# SBX_connector_outline.net
KiCad netlist of a schematic drawn in EAGLE
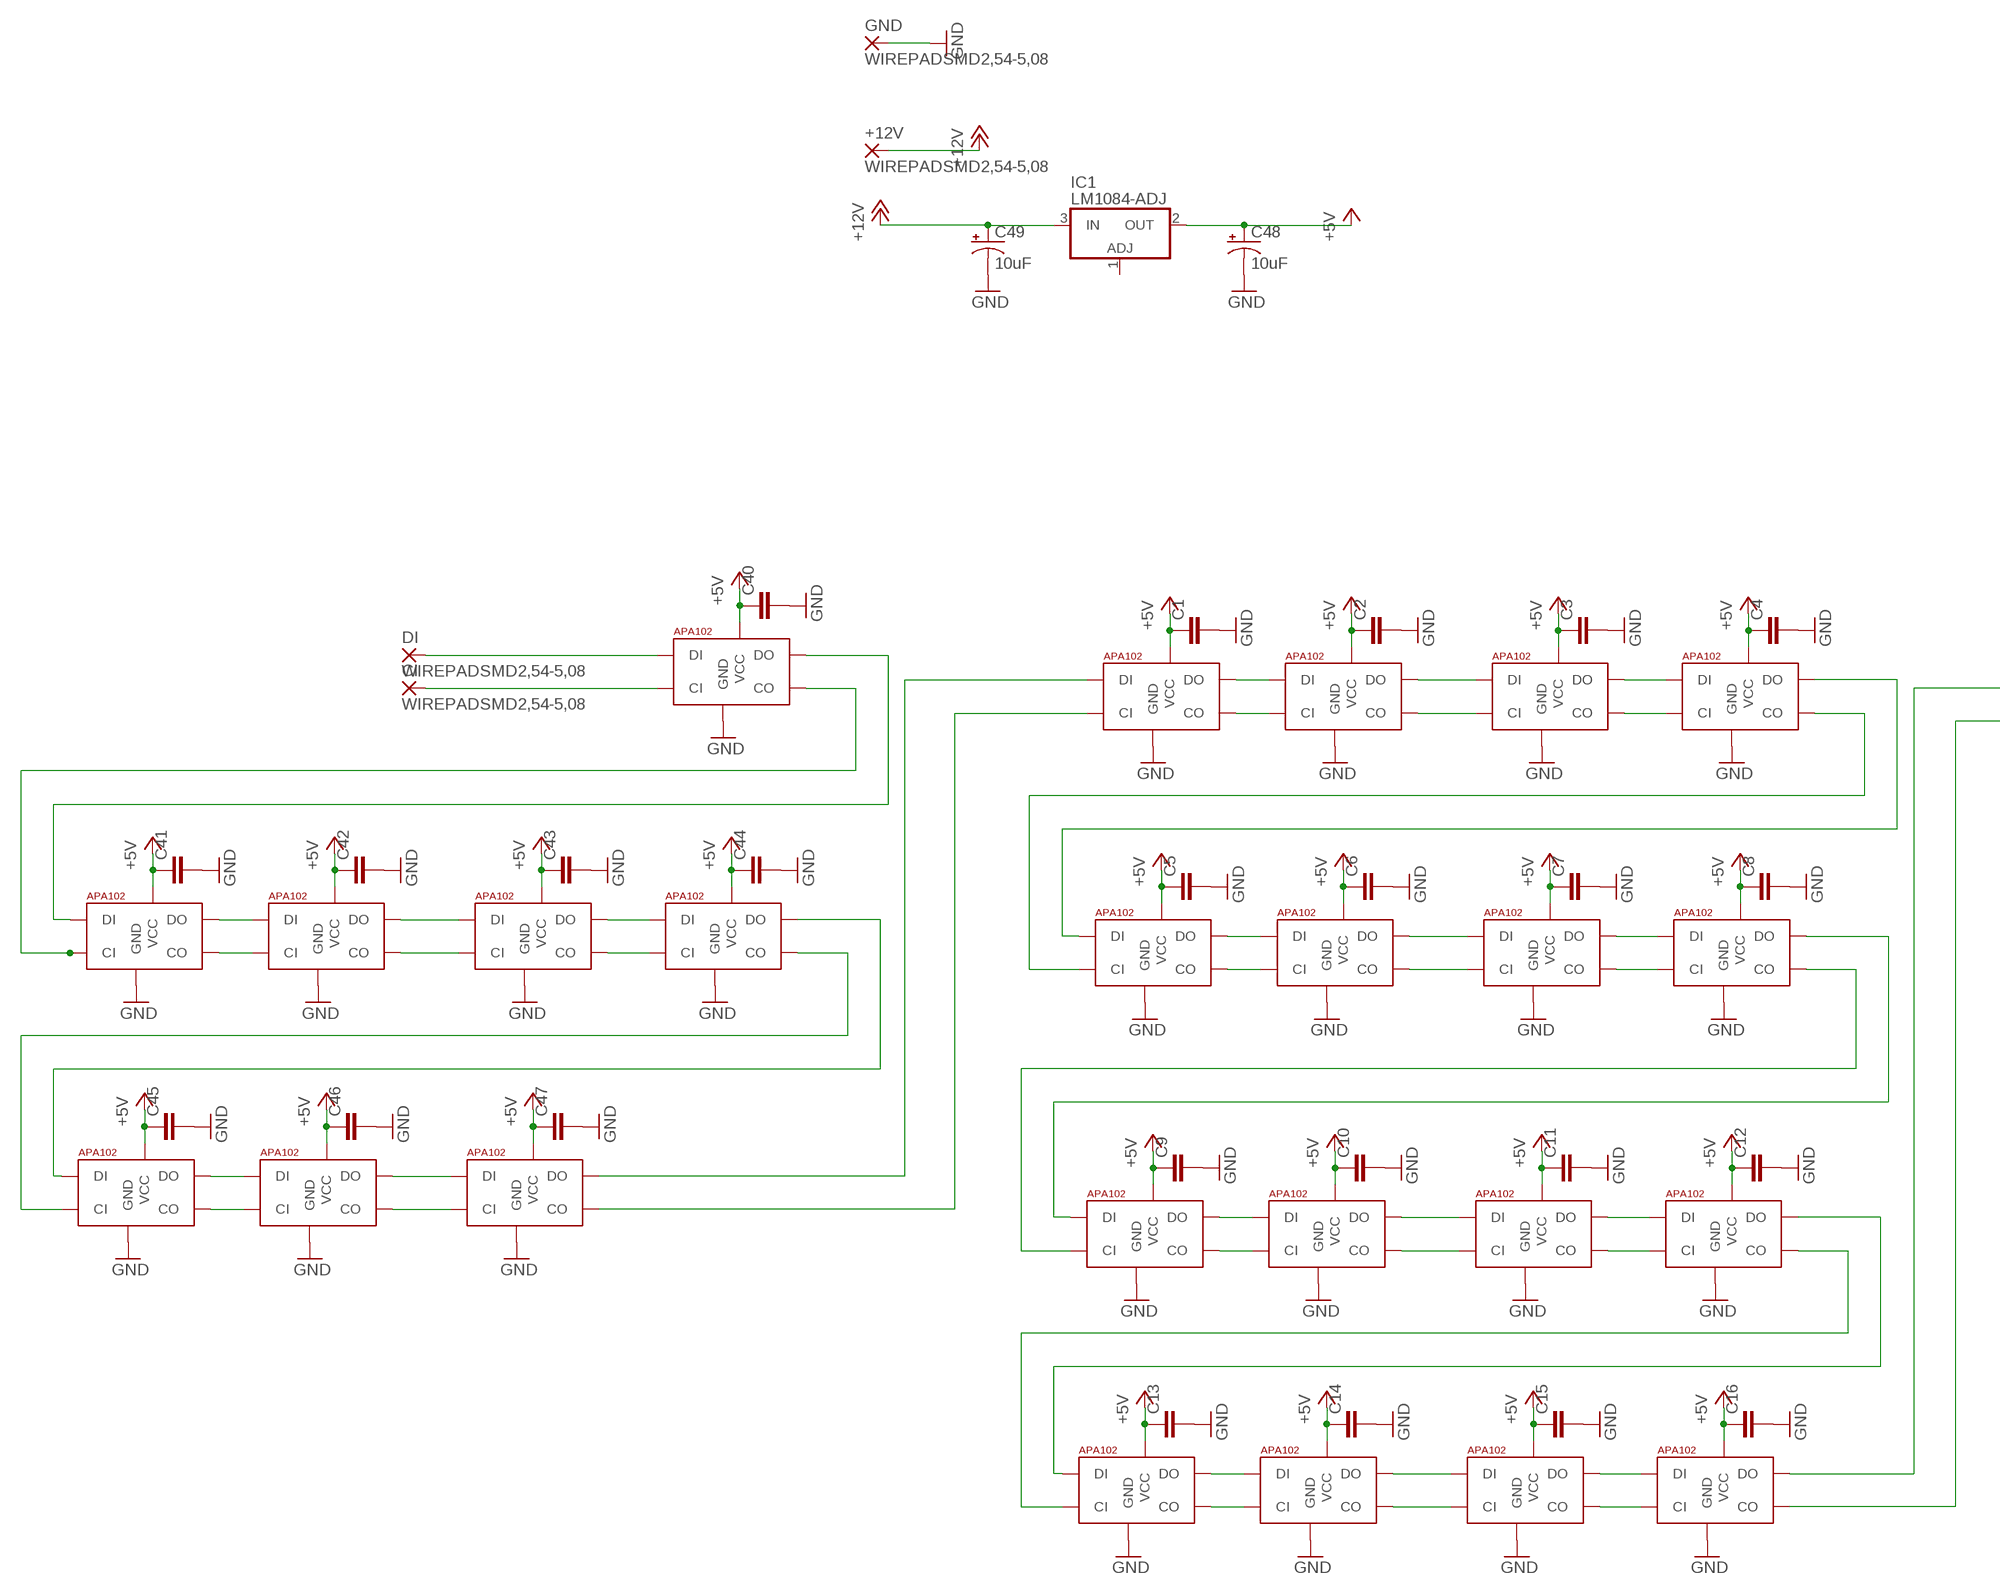
[diagram p0: schematic, sheet 1, part 1 of 2]
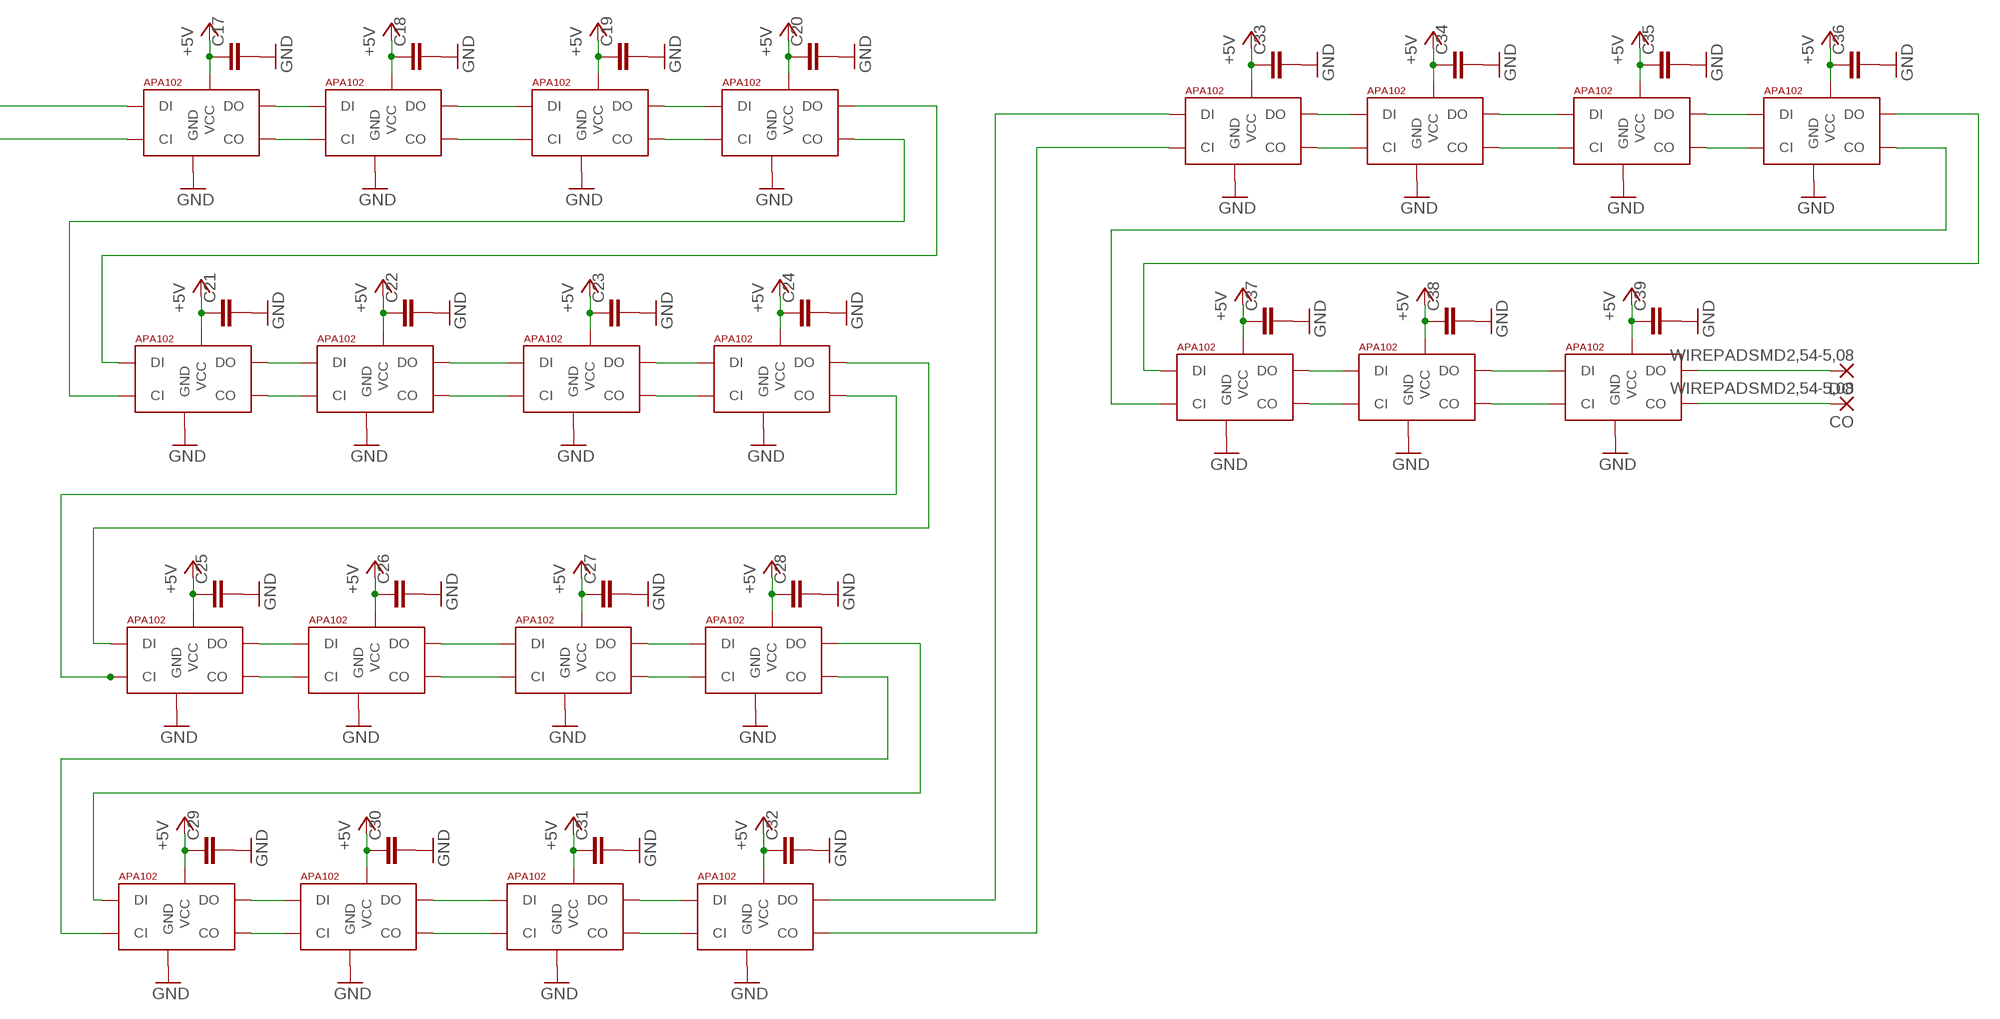
[diagram p1: schematic, sheet 1, part 2 of 2]

(export (version "E")
  (design (tool "Eeschema 10.0.6"))
  (components
    (comp (ref "+12V")
      (value "WIREPADSMD2,54-5,08")
      (footprint "eagle-import:SMD2,54-5,08")
      (libsource (lib "eagle-import") (part "WIREPADSMD2,54-5,08"))
    )
    (comp (ref "C1")
      (value "CAP0603-CAP")
      (footprint "eagle-import:0603-CAP")
      (libsource (lib "eagle-import") (part "CAP0603-CAP"))
    )
    (comp (ref "C2")
      (value "CAP0603-CAP")
      (footprint "eagle-import:0603-CAP")
      (libsource (lib "eagle-import") (part "CAP0603-CAP"))
    )
    (comp (ref "C3")
      (value "CAP0603-CAP")
      (footprint "eagle-import:0603-CAP")
      (libsource (lib "eagle-import") (part "CAP0603-CAP"))
    )
    (comp (ref "C4")
      (value "CAP0603-CAP")
      (footprint "eagle-import:0603-CAP")
      (libsource (lib "eagle-import") (part "CAP0603-CAP"))
    )
    (comp (ref "C5")
      (value "CAP0603-CAP")
      (footprint "eagle-import:0603-CAP")
      (libsource (lib "eagle-import") (part "CAP0603-CAP"))
    )
    (comp (ref "C6")
      (value "CAP0603-CAP")
      (footprint "eagle-import:0603-CAP")
      (libsource (lib "eagle-import") (part "CAP0603-CAP"))
    )
    (comp (ref "C7")
      (value "CAP0603-CAP")
      (footprint "eagle-import:0603-CAP")
      (libsource (lib "eagle-import") (part "CAP0603-CAP"))
    )
    (comp (ref "C8")
      (value "CAP0603-CAP")
      (footprint "eagle-import:0603-CAP")
      (libsource (lib "eagle-import") (part "CAP0603-CAP"))
    )
    (comp (ref "C9")
      (value "CAP0603-CAP")
      (footprint "eagle-import:0603-CAP")
      (libsource (lib "eagle-import") (part "CAP0603-CAP"))
    )
    (comp (ref "C10")
      (value "CAP0603-CAP")
      (footprint "eagle-import:0603-CAP")
      (libsource (lib "eagle-import") (part "CAP0603-CAP"))
    )
    (comp (ref "C11")
      (value "CAP0603-CAP")
      (footprint "eagle-import:0603-CAP")
      (libsource (lib "eagle-import") (part "CAP0603-CAP"))
    )
    (comp (ref "C12")
      (value "CAP0603-CAP")
      (footprint "eagle-import:0603-CAP")
      (libsource (lib "eagle-import") (part "CAP0603-CAP"))
    )
    (comp (ref "C13")
      (value "CAP0603-CAP")
      (footprint "eagle-import:0603-CAP")
      (libsource (lib "eagle-import") (part "CAP0603-CAP"))
    )
    (comp (ref "C14")
      (value "CAP0603-CAP")
      (footprint "eagle-import:0603-CAP")
      (libsource (lib "eagle-import") (part "CAP0603-CAP"))
    )
    (comp (ref "C15")
      (value "CAP0603-CAP")
      (footprint "eagle-import:0603-CAP")
      (libsource (lib "eagle-import") (part "CAP0603-CAP"))
    )
    (comp (ref "C16")
      (value "CAP0603-CAP")
      (footprint "eagle-import:0603-CAP")
      (libsource (lib "eagle-import") (part "CAP0603-CAP"))
    )
    (comp (ref "C17")
      (value "CAP0603-CAP")
      (footprint "eagle-import:0603-CAP")
      (libsource (lib "eagle-import") (part "CAP0603-CAP"))
    )
    (comp (ref "C18")
      (value "CAP0603-CAP")
      (footprint "eagle-import:0603-CAP")
      (libsource (lib "eagle-import") (part "CAP0603-CAP"))
    )
    (comp (ref "C19")
      (value "CAP0603-CAP")
      (footprint "eagle-import:0603-CAP")
      (libsource (lib "eagle-import") (part "CAP0603-CAP"))
    )
    (comp (ref "C20")
      (value "CAP0603-CAP")
      (footprint "eagle-import:0603-CAP")
      (libsource (lib "eagle-import") (part "CAP0603-CAP"))
    )
    (comp (ref "C21")
      (value "CAP0603-CAP")
      (footprint "eagle-import:0603-CAP")
      (libsource (lib "eagle-import") (part "CAP0603-CAP"))
    )
    (comp (ref "C22")
      (value "CAP0603-CAP")
      (footprint "eagle-import:0603-CAP")
      (libsource (lib "eagle-import") (part "CAP0603-CAP"))
    )
    (comp (ref "C23")
      (value "CAP0603-CAP")
      (footprint "eagle-import:0603-CAP")
      (libsource (lib "eagle-import") (part "CAP0603-CAP"))
    )
    (comp (ref "C24")
      (value "CAP0603-CAP")
      (footprint "eagle-import:0603-CAP")
      (libsource (lib "eagle-import") (part "CAP0603-CAP"))
    )
    (comp (ref "C25")
      (value "CAP0603-CAP")
      (footprint "eagle-import:0603-CAP")
      (libsource (lib "eagle-import") (part "CAP0603-CAP"))
    )
    (comp (ref "C26")
      (value "CAP0603-CAP")
      (footprint "eagle-import:0603-CAP")
      (libsource (lib "eagle-import") (part "CAP0603-CAP"))
    )
    (comp (ref "C27")
      (value "CAP0603-CAP")
      (footprint "eagle-import:0603-CAP")
      (libsource (lib "eagle-import") (part "CAP0603-CAP"))
    )
    (comp (ref "C28")
      (value "CAP0603-CAP")
      (footprint "eagle-import:0603-CAP")
      (libsource (lib "eagle-import") (part "CAP0603-CAP"))
    )
    (comp (ref "C29")
      (value "CAP0603-CAP")
      (footprint "eagle-import:0603-CAP")
      (libsource (lib "eagle-import") (part "CAP0603-CAP"))
    )
    (comp (ref "C30")
      (value "CAP0603-CAP")
      (footprint "eagle-import:0603-CAP")
      (libsource (lib "eagle-import") (part "CAP0603-CAP"))
    )
    (comp (ref "C31")
      (value "CAP0603-CAP")
      (footprint "eagle-import:0603-CAP")
      (libsource (lib "eagle-import") (part "CAP0603-CAP"))
    )
    (comp (ref "C32")
      (value "CAP0603-CAP")
      (footprint "eagle-import:0603-CAP")
      (libsource (lib "eagle-import") (part "CAP0603-CAP"))
    )
    (comp (ref "C33")
      (value "CAP0603-CAP")
      (footprint "eagle-import:0603-CAP")
      (libsource (lib "eagle-import") (part "CAP0603-CAP"))
    )
    (comp (ref "C34")
      (value "CAP0603-CAP")
      (footprint "eagle-import:0603-CAP")
      (libsource (lib "eagle-import") (part "CAP0603-CAP"))
    )
    (comp (ref "C35")
      (value "CAP0603-CAP")
      (footprint "eagle-import:0603-CAP")
      (libsource (lib "eagle-import") (part "CAP0603-CAP"))
    )
    (comp (ref "C36")
      (value "CAP0603-CAP")
      (footprint "eagle-import:0603-CAP")
      (libsource (lib "eagle-import") (part "CAP0603-CAP"))
    )
    (comp (ref "C37")
      (value "CAP0603-CAP")
      (footprint "eagle-import:0603-CAP")
      (libsource (lib "eagle-import") (part "CAP0603-CAP"))
    )
    (comp (ref "C38")
      (value "CAP0603-CAP")
      (footprint "eagle-import:0603-CAP")
      (libsource (lib "eagle-import") (part "CAP0603-CAP"))
    )
    (comp (ref "C39")
      (value "CAP0603-CAP")
      (footprint "eagle-import:0603-CAP")
      (libsource (lib "eagle-import") (part "CAP0603-CAP"))
    )
    (comp (ref "C40")
      (value "CAP0603-CAP")
      (footprint "eagle-import:0603-CAP")
      (libsource (lib "eagle-import") (part "CAP0603-CAP"))
    )
    (comp (ref "C41")
      (value "CAP0603-CAP")
      (footprint "eagle-import:0603-CAP")
      (libsource (lib "eagle-import") (part "CAP0603-CAP"))
    )
    (comp (ref "C42")
      (value "CAP0603-CAP")
      (footprint "eagle-import:0603-CAP")
      (libsource (lib "eagle-import") (part "CAP0603-CAP"))
    )
    (comp (ref "C43")
      (value "CAP0603-CAP")
      (footprint "eagle-import:0603-CAP")
      (libsource (lib "eagle-import") (part "CAP0603-CAP"))
    )
    (comp (ref "C44")
      (value "CAP0603-CAP")
      (footprint "eagle-import:0603-CAP")
      (libsource (lib "eagle-import") (part "CAP0603-CAP"))
    )
    (comp (ref "C45")
      (value "CAP0603-CAP")
      (footprint "eagle-import:0603-CAP")
      (libsource (lib "eagle-import") (part "CAP0603-CAP"))
    )
    (comp (ref "C46")
      (value "CAP0603-CAP")
      (footprint "eagle-import:0603-CAP")
      (libsource (lib "eagle-import") (part "CAP0603-CAP"))
    )
    (comp (ref "C47")
      (value "CAP0603-CAP")
      (footprint "eagle-import:0603-CAP")
      (libsource (lib "eagle-import") (part "CAP0603-CAP"))
    )
    (comp (ref "C48")
      (value "10uF")
      (footprint "eagle-import:EIA3216")
      (libsource (lib "eagle-import") (part "10UF-TANT"))
    )
    (comp (ref "C49")
      (value "10uF")
      (footprint "eagle-import:EIA3216")
      (libsource (lib "eagle-import") (part "10UF-TANT"))
    )
    (comp (ref "CI")
      (value "WIREPADSMD2,54-5,08")
      (footprint "eagle-import:SMD2,54-5,08")
      (libsource (lib "eagle-import") (part "WIREPADSMD2,54-5,08"))
    )
    (comp (ref "CO")
      (value "WIREPADSMD2,54-5,08")
      (footprint "eagle-import:SMD2,54-5,08")
      (libsource (lib "eagle-import") (part "WIREPADSMD2,54-5,08"))
    )
    (comp (ref "DI")
      (value "WIREPADSMD2,54-5,08")
      (footprint "eagle-import:SMD2,54-5,08")
      (libsource (lib "eagle-import") (part "WIREPADSMD2,54-5,08"))
    )
    (comp (ref "DO")
      (value "WIREPADSMD2,54-5,08")
      (footprint "eagle-import:SMD2,54-5,08")
      (libsource (lib "eagle-import") (part "WIREPADSMD2,54-5,08"))
    )
    (comp (ref "GND")
      (value "WIREPADSMD2,54-5,08")
      (footprint "eagle-import:SMD2,54-5,08")
      (libsource (lib "eagle-import") (part "WIREPADSMD2,54-5,08"))
    )
    (comp (ref "IC1")
      (value "LM1084-ADJ")
      (footprint "eagle-import:TO263-3")
      (libsource (lib "eagle-import") (part "LM1084-ADJ"))
    )
    (comp (ref "U$1")
      (value "APA1025050")
      (footprint "eagle-import:APA102_5050")
      (libsource (lib "eagle-import") (part "APA1025050"))
    )
    (comp (ref "U$2")
      (value "APA1025050")
      (footprint "eagle-import:APA102_5050")
      (libsource (lib "eagle-import") (part "APA1025050"))
    )
    (comp (ref "U$3")
      (value "APA1025050")
      (footprint "eagle-import:APA102_5050")
      (libsource (lib "eagle-import") (part "APA1025050"))
    )
    (comp (ref "U$4")
      (value "APA1025050")
      (footprint "eagle-import:APA102_5050")
      (libsource (lib "eagle-import") (part "APA1025050"))
    )
    (comp (ref "U$5")
      (value "APA1025050")
      (footprint "eagle-import:APA102_5050")
      (libsource (lib "eagle-import") (part "APA1025050"))
    )
    (comp (ref "U$6")
      (value "APA1025050")
      (footprint "eagle-import:APA102_5050")
      (libsource (lib "eagle-import") (part "APA1025050"))
    )
    (comp (ref "U$7")
      (value "APA1025050")
      (footprint "eagle-import:APA102_5050")
      (libsource (lib "eagle-import") (part "APA1025050"))
    )
    (comp (ref "U$8")
      (value "APA1025050")
      (footprint "eagle-import:APA102_5050")
      (libsource (lib "eagle-import") (part "APA1025050"))
    )
    (comp (ref "U$9")
      (value "APA1025050")
      (footprint "eagle-import:APA102_5050")
      (libsource (lib "eagle-import") (part "APA1025050"))
    )
    (comp (ref "U$10")
      (value "APA1025050")
      (footprint "eagle-import:APA102_5050")
      (libsource (lib "eagle-import") (part "APA1025050"))
    )
    (comp (ref "U$11")
      (value "APA1025050")
      (footprint "eagle-import:APA102_5050")
      (libsource (lib "eagle-import") (part "APA1025050"))
    )
    (comp (ref "U$12")
      (value "APA1025050")
      (footprint "eagle-import:APA102_5050")
      (libsource (lib "eagle-import") (part "APA1025050"))
    )
    (comp (ref "U$13")
      (value "APA1025050")
      (footprint "eagle-import:APA102_5050")
      (libsource (lib "eagle-import") (part "APA1025050"))
    )
    (comp (ref "U$14")
      (value "APA1025050")
      (footprint "eagle-import:APA102_5050")
      (libsource (lib "eagle-import") (part "APA1025050"))
    )
    (comp (ref "U$15")
      (value "APA1025050")
      (footprint "eagle-import:APA102_5050")
      (libsource (lib "eagle-import") (part "APA1025050"))
    )
    (comp (ref "U$16")
      (value "APA1025050")
      (footprint "eagle-import:APA102_5050")
      (libsource (lib "eagle-import") (part "APA1025050"))
    )
    (comp (ref "U$17")
      (value "APA1025050")
      (footprint "eagle-import:APA102_5050")
      (libsource (lib "eagle-import") (part "APA1025050"))
    )
    (comp (ref "U$18")
      (value "APA1025050")
      (footprint "eagle-import:APA102_5050")
      (libsource (lib "eagle-import") (part "APA1025050"))
    )
    (comp (ref "U$19")
      (value "APA1025050")
      (footprint "eagle-import:APA102_5050")
      (libsource (lib "eagle-import") (part "APA1025050"))
    )
    (comp (ref "U$20")
      (value "APA1025050")
      (footprint "eagle-import:APA102_5050")
      (libsource (lib "eagle-import") (part "APA1025050"))
    )
    (comp (ref "U$21")
      (value "APA1025050")
      (footprint "eagle-import:APA102_5050")
      (libsource (lib "eagle-import") (part "APA1025050"))
    )
    (comp (ref "U$22")
      (value "APA1025050")
      (footprint "eagle-import:APA102_5050")
      (libsource (lib "eagle-import") (part "APA1025050"))
    )
    (comp (ref "U$23")
      (value "APA1025050")
      (footprint "eagle-import:APA102_5050")
      (libsource (lib "eagle-import") (part "APA1025050"))
    )
    (comp (ref "U$24")
      (value "APA1025050")
      (footprint "eagle-import:APA102_5050")
      (libsource (lib "eagle-import") (part "APA1025050"))
    )
    (comp (ref "U$25")
      (value "APA1025050")
      (footprint "eagle-import:APA102_5050")
      (libsource (lib "eagle-import") (part "APA1025050"))
    )
    (comp (ref "U$26")
      (value "APA1025050")
      (footprint "eagle-import:APA102_5050")
      (libsource (lib "eagle-import") (part "APA1025050"))
    )
    (comp (ref "U$27")
      (value "APA1025050")
      (footprint "eagle-import:APA102_5050")
      (libsource (lib "eagle-import") (part "APA1025050"))
    )
    (comp (ref "U$28")
      (value "APA1025050")
      (footprint "eagle-import:APA102_5050")
      (libsource (lib "eagle-import") (part "APA1025050"))
    )
    (comp (ref "U$29")
      (value "APA1025050")
      (footprint "eagle-import:APA102_5050")
      (libsource (lib "eagle-import") (part "APA1025050"))
    )
    (comp (ref "U$30")
      (value "APA1025050")
      (footprint "eagle-import:APA102_5050")
      (libsource (lib "eagle-import") (part "APA1025050"))
    )
    (comp (ref "U$31")
      (value "APA1025050")
      (footprint "eagle-import:APA102_5050")
      (libsource (lib "eagle-import") (part "APA1025050"))
    )
    (comp (ref "U$32")
      (value "APA1025050")
      (footprint "eagle-import:APA102_5050")
      (libsource (lib "eagle-import") (part "APA1025050"))
    )
    (comp (ref "U$33")
      (value "APA1025050")
      (footprint "eagle-import:APA102_5050")
      (libsource (lib "eagle-import") (part "APA1025050"))
    )
    (comp (ref "U$34")
      (value "APA1025050")
      (footprint "eagle-import:APA102_5050")
      (libsource (lib "eagle-import") (part "APA1025050"))
    )
    (comp (ref "U$35")
      (value "APA1025050")
      (footprint "eagle-import:APA102_5050")
      (libsource (lib "eagle-import") (part "APA1025050"))
    )
    (comp (ref "U$36")
      (value "APA1025050")
      (footprint "eagle-import:APA102_5050")
      (libsource (lib "eagle-import") (part "APA1025050"))
    )
    (comp (ref "U$37")
      (value "APA1025050")
      (footprint "eagle-import:APA102_5050")
      (libsource (lib "eagle-import") (part "APA1025050"))
    )
    (comp (ref "U$38")
      (value "APA1025050")
      (footprint "eagle-import:APA102_5050")
      (libsource (lib "eagle-import") (part "APA1025050"))
    )
    (comp (ref "U$39")
      (value "APA1025050")
      (footprint "eagle-import:APA102_5050")
      (libsource (lib "eagle-import") (part "APA1025050"))
    )
    (comp (ref "U$40")
      (value "APA1025050")
      (footprint "eagle-import:APA102_5050")
      (libsource (lib "eagle-import") (part "APA1025050"))
    )
    (comp (ref "U$41")
      (value "APA1025050")
      (footprint "eagle-import:APA102_5050")
      (libsource (lib "eagle-import") (part "APA1025050"))
    )
    (comp (ref "U$42")
      (value "APA1025050")
      (footprint "eagle-import:APA102_5050")
      (libsource (lib "eagle-import") (part "APA1025050"))
    )
    (comp (ref "U$43")
      (value "APA1025050")
      (footprint "eagle-import:APA102_5050")
      (libsource (lib "eagle-import") (part "APA1025050"))
    )
    (comp (ref "U$44")
      (value "APA1025050")
      (footprint "eagle-import:APA102_5050")
      (libsource (lib "eagle-import") (part "APA1025050"))
    )
    (comp (ref "U$45")
      (value "APA1025050")
      (footprint "eagle-import:APA102_5050")
      (libsource (lib "eagle-import") (part "APA1025050"))
    )
    (comp (ref "U$46")
      (value "APA1025050")
      (footprint "eagle-import:APA102_5050")
      (libsource (lib "eagle-import") (part "APA1025050"))
    )
    (comp (ref "U$47")
      (value "APA1025050")
      (footprint "eagle-import:APA102_5050")
      (libsource (lib "eagle-import") (part "APA1025050"))
    )
  )
  (nets
    (net (code "1") (name "+5V") (class "Default")
      (node (ref "C1") (pin "1") (pinfunction "1_1") (pintype "passive"))
      (node (ref "C10") (pin "1") (pinfunction "1_1") (pintype "passive"))
      (node (ref "C11") (pin "1") (pinfunction "1_1") (pintype "passive"))
      (node (ref "C12") (pin "1") (pinfunction "1_1") (pintype "passive"))
      (node (ref "C13") (pin "1") (pinfunction "1_1") (pintype "passive"))
      (node (ref "C14") (pin "1") (pinfunction "1_1") (pintype "passive"))
      (node (ref "C15") (pin "1") (pinfunction "1_1") (pintype "passive"))
      (node (ref "C16") (pin "1") (pinfunction "1_1") (pintype "passive"))
      (node (ref "C17") (pin "1") (pinfunction "1_1") (pintype "passive"))
      (node (ref "C18") (pin "1") (pinfunction "1_1") (pintype "passive"))
      (node (ref "C19") (pin "1") (pinfunction "1_1") (pintype "passive"))
      (node (ref "C2") (pin "1") (pinfunction "1_1") (pintype "passive"))
      (node (ref "C20") (pin "1") (pinfunction "1_1") (pintype "passive"))
      (node (ref "C21") (pin "1") (pinfunction "1_1") (pintype "passive"))
      (node (ref "C22") (pin "1") (pinfunction "1_1") (pintype "passive"))
      (node (ref "C23") (pin "1") (pinfunction "1_1") (pintype "passive"))
      (node (ref "C24") (pin "1") (pinfunction "1_1") (pintype "passive"))
      (node (ref "C25") (pin "1") (pinfunction "1_1") (pintype "passive"))
      (node (ref "C26") (pin "1") (pinfunction "1_1") (pintype "passive"))
      (node (ref "C27") (pin "1") (pinfunction "1_1") (pintype "passive"))
      (node (ref "C28") (pin "1") (pinfunction "1_1") (pintype "passive"))
      (node (ref "C29") (pin "1") (pinfunction "1_1") (pintype "passive"))
      (node (ref "C3") (pin "1") (pinfunction "1_1") (pintype "passive"))
      (node (ref "C30") (pin "1") (pinfunction "1_1") (pintype "passive"))
      (node (ref "C31") (pin "1") (pinfunction "1_1") (pintype "passive"))
      (node (ref "C32") (pin "1") (pinfunction "1_1") (pintype "passive"))
      (node (ref "C33") (pin "1") (pinfunction "1_1") (pintype "passive"))
      (node (ref "C34") (pin "1") (pinfunction "1_1") (pintype "passive"))
      (node (ref "C35") (pin "1") (pinfunction "1_1") (pintype "passive"))
      (node (ref "C36") (pin "1") (pinfunction "1_1") (pintype "passive"))
      (node (ref "C37") (pin "1") (pinfunction "1_1") (pintype "passive"))
      (node (ref "C38") (pin "1") (pinfunction "1_1") (pintype "passive"))
      (node (ref "C39") (pin "1") (pinfunction "1_1") (pintype "passive"))
      (node (ref "C4") (pin "1") (pinfunction "1_1") (pintype "passive"))
      (node (ref "C40") (pin "1") (pinfunction "1_1") (pintype "passive"))
      (node (ref "C41") (pin "1") (pinfunction "1_1") (pintype "passive"))
      (node (ref "C42") (pin "1") (pinfunction "1_1") (pintype "passive"))
      (node (ref "C43") (pin "1") (pinfunction "1_1") (pintype "passive"))
      (node (ref "C44") (pin "1") (pinfunction "1_1") (pintype "passive"))
      (node (ref "C45") (pin "1") (pinfunction "1_1") (pintype "passive"))
      (node (ref "C46") (pin "1") (pinfunction "1_1") (pintype "passive"))
      (node (ref "C47") (pin "1") (pinfunction "1_1") (pintype "passive"))
      (node (ref "C48") (pin "A") (pinfunction "+_A") (pintype "passive"))
      (node (ref "C5") (pin "1") (pinfunction "1_1") (pintype "passive"))
      (node (ref "C6") (pin "1") (pinfunction "1_1") (pintype "passive"))
      (node (ref "C7") (pin "1") (pinfunction "1_1") (pintype "passive"))
      (node (ref "C8") (pin "1") (pinfunction "1_1") (pintype "passive"))
      (node (ref "C9") (pin "1") (pinfunction "1_1") (pintype "passive"))
      (node (ref "IC1") (pin "2") (pinfunction "OUT_2") (pintype "output"))
      (node (ref "U$1") (pin "1") (pinfunction "VCC_1") (pintype "bidirectional"))
      (node (ref "U$10") (pin "1") (pinfunction "VCC_1") (pintype "bidirectional"))
      (node (ref "U$11") (pin "1") (pinfunction "VCC_1") (pintype "bidirectional"))
      (node (ref "U$12") (pin "1") (pinfunction "VCC_1") (pintype "bidirectional"))
      (node (ref "U$13") (pin "1") (pinfunction "VCC_1") (pintype "bidirectional"))
      (node (ref "U$14") (pin "1") (pinfunction "VCC_1") (pintype "bidirectional"))
      (node (ref "U$15") (pin "1") (pinfunction "VCC_1") (pintype "bidirectional"))
      (node (ref "U$16") (pin "1") (pinfunction "VCC_1") (pintype "bidirectional"))
      (node (ref "U$17") (pin "1") (pinfunction "VCC_1") (pintype "bidirectional"))
      (node (ref "U$18") (pin "1") (pinfunction "VCC_1") (pintype "bidirectional"))
      (node (ref "U$19") (pin "1") (pinfunction "VCC_1") (pintype "bidirectional"))
      (node (ref "U$2") (pin "1") (pinfunction "VCC_1") (pintype "bidirectional"))
      (node (ref "U$20") (pin "1") (pinfunction "VCC_1") (pintype "bidirectional"))
      (node (ref "U$21") (pin "1") (pinfunction "VCC_1") (pintype "bidirectional"))
      (node (ref "U$22") (pin "1") (pinfunction "VCC_1") (pintype "bidirectional"))
      (node (ref "U$23") (pin "1") (pinfunction "VCC_1") (pintype "bidirectional"))
      (node (ref "U$24") (pin "1") (pinfunction "VCC_1") (pintype "bidirectional"))
      (node (ref "U$25") (pin "1") (pinfunction "VCC_1") (pintype "bidirectional"))
      (node (ref "U$26") (pin "1") (pinfunction "VCC_1") (pintype "bidirectional"))
      (node (ref "U$27") (pin "1") (pinfunction "VCC_1") (pintype "bidirectional"))
      (node (ref "U$28") (pin "1") (pinfunction "VCC_1") (pintype "bidirectional"))
      (node (ref "U$29") (pin "1") (pinfunction "VCC_1") (pintype "bidirectional"))
      (node (ref "U$3") (pin "1") (pinfunction "VCC_1") (pintype "bidirectional"))
      (node (ref "U$30") (pin "1") (pinfunction "VCC_1") (pintype "bidirectional"))
      (node (ref "U$31") (pin "1") (pinfunction "VCC_1") (pintype "bidirectional"))
      (node (ref "U$32") (pin "1") (pinfunction "VCC_1") (pintype "bidirectional"))
      (node (ref "U$33") (pin "1") (pinfunction "VCC_1") (pintype "bidirectional"))
      (node (ref "U$34") (pin "1") (pinfunction "VCC_1") (pintype "bidirectional"))
      (node (ref "U$35") (pin "1") (pinfunction "VCC_1") (pintype "bidirectional"))
      (node (ref "U$36") (pin "1") (pinfunction "VCC_1") (pintype "bidirectional"))
      (node (ref "U$37") (pin "1") (pinfunction "VCC_1") (pintype "bidirectional"))
      (node (ref "U$38") (pin "1") (pinfunction "VCC_1") (pintype "bidirectional"))
      (node (ref "U$39") (pin "1") (pinfunction "VCC_1") (pintype "bidirectional"))
      (node (ref "U$4") (pin "1") (pinfunction "VCC_1") (pintype "bidirectional"))
      (node (ref "U$40") (pin "1") (pinfunction "VCC_1") (pintype "bidirectional"))
      (node (ref "U$41") (pin "1") (pinfunction "VCC_1") (pintype "bidirectional"))
      (node (ref "U$42") (pin "1") (pinfunction "VCC_1") (pintype "bidirectional"))
      (node (ref "U$43") (pin "1") (pinfunction "VCC_1") (pintype "bidirectional"))
      (node (ref "U$44") (pin "1") (pinfunction "VCC_1") (pintype "bidirectional"))
      (node (ref "U$45") (pin "1") (pinfunction "VCC_1") (pintype "bidirectional"))
      (node (ref "U$46") (pin "1") (pinfunction "VCC_1") (pintype "bidirectional"))
      (node (ref "U$47") (pin "1") (pinfunction "VCC_1") (pintype "bidirectional"))
      (node (ref "U$5") (pin "1") (pinfunction "VCC_1") (pintype "bidirectional"))
      (node (ref "U$6") (pin "1") (pinfunction "VCC_1") (pintype "bidirectional"))
      (node (ref "U$7") (pin "1") (pinfunction "VCC_1") (pintype "bidirectional"))
      (node (ref "U$8") (pin "1") (pinfunction "VCC_1") (pintype "bidirectional"))
      (node (ref "U$9") (pin "1") (pinfunction "VCC_1") (pintype "bidirectional"))
    )
    (net (code "2") (name "+12V") (class "Default")
      (node (ref "+12V") (pin "1") (pinfunction "P_1") (pintype "passive"))
      (node (ref "C49") (pin "A") (pinfunction "+_A") (pintype "passive"))
      (node (ref "IC1") (pin "3") (pinfunction "IN_3") (pintype "input"))
    )
    (net (code "3") (name "GND") (class "Default")
      (node (ref "C1") (pin "2") (pinfunction "2_2") (pintype "passive"))
      (node (ref "C10") (pin "2") (pinfunction "2_2") (pintype "passive"))
      (node (ref "C11") (pin "2") (pinfunction "2_2") (pintype "passive"))
      (node (ref "C12") (pin "2") (pinfunction "2_2") (pintype "passive"))
      (node (ref "C13") (pin "2") (pinfunction "2_2") (pintype "passive"))
      (node (ref "C14") (pin "2") (pinfunction "2_2") (pintype "passive"))
      (node (ref "C15") (pin "2") (pinfunction "2_2") (pintype "passive"))
      (node (ref "C16") (pin "2") (pinfunction "2_2") (pintype "passive"))
      (node (ref "C17") (pin "2") (pinfunction "2_2") (pintype "passive"))
      (node (ref "C18") (pin "2") (pinfunction "2_2") (pintype "passive"))
      (node (ref "C19") (pin "2") (pinfunction "2_2") (pintype "passive"))
      (node (ref "C2") (pin "2") (pinfunction "2_2") (pintype "passive"))
      (node (ref "C20") (pin "2") (pinfunction "2_2") (pintype "passive"))
      (node (ref "C21") (pin "2") (pinfunction "2_2") (pintype "passive"))
      (node (ref "C22") (pin "2") (pinfunction "2_2") (pintype "passive"))
      (node (ref "C23") (pin "2") (pinfunction "2_2") (pintype "passive"))
      (node (ref "C24") (pin "2") (pinfunction "2_2") (pintype "passive"))
      (node (ref "C25") (pin "2") (pinfunction "2_2") (pintype "passive"))
      (node (ref "C26") (pin "2") (pinfunction "2_2") (pintype "passive"))
      (node (ref "C27") (pin "2") (pinfunction "2_2") (pintype "passive"))
      (node (ref "C28") (pin "2") (pinfunction "2_2") (pintype "passive"))
      (node (ref "C29") (pin "2") (pinfunction "2_2") (pintype "passive"))
      (node (ref "C3") (pin "2") (pinfunction "2_2") (pintype "passive"))
      (node (ref "C30") (pin "2") (pinfunction "2_2") (pintype "passive"))
      (node (ref "C31") (pin "2") (pinfunction "2_2") (pintype "passive"))
      (node (ref "C32") (pin "2") (pinfunction "2_2") (pintype "passive"))
      (node (ref "C33") (pin "2") (pinfunction "2_2") (pintype "passive"))
      (node (ref "C34") (pin "2") (pinfunction "2_2") (pintype "passive"))
      (node (ref "C35") (pin "2") (pinfunction "2_2") (pintype "passive"))
      (node (ref "C36") (pin "2") (pinfunction "2_2") (pintype "passive"))
      (node (ref "C37") (pin "2") (pinfunction "2_2") (pintype "passive"))
      (node (ref "C38") (pin "2") (pinfunction "2_2") (pintype "passive"))
      (node (ref "C39") (pin "2") (pinfunction "2_2") (pintype "passive"))
      (node (ref "C4") (pin "2") (pinfunction "2_2") (pintype "passive"))
      (node (ref "C40") (pin "2") (pinfunction "2_2") (pintype "passive"))
      (node (ref "C41") (pin "2") (pinfunction "2_2") (pintype "passive"))
      (node (ref "C42") (pin "2") (pinfunction "2_2") (pintype "passive"))
      (node (ref "C43") (pin "2") (pinfunction "2_2") (pintype "passive"))
      (node (ref "C44") (pin "2") (pinfunction "2_2") (pintype "passive"))
      (node (ref "C45") (pin "2") (pinfunction "2_2") (pintype "passive"))
      (node (ref "C46") (pin "2") (pinfunction "2_2") (pintype "passive"))
      (node (ref "C47") (pin "2") (pinfunction "2_2") (pintype "passive"))
      (node (ref "C48") (pin "C") (pinfunction "-_C") (pintype "passive"))
      (node (ref "C49") (pin "C") (pinfunction "-_C") (pintype "passive"))
      (node (ref "C5") (pin "2") (pinfunction "2_2") (pintype "passive"))
      (node (ref "C6") (pin "2") (pinfunction "2_2") (pintype "passive"))
      (node (ref "C7") (pin "2") (pinfunction "2_2") (pintype "passive"))
      (node (ref "C8") (pin "2") (pinfunction "2_2") (pintype "passive"))
      (node (ref "C9") (pin "2") (pinfunction "2_2") (pintype "passive"))
      (node (ref "GND") (pin "1") (pinfunction "P_1") (pintype "passive"))
      (node (ref "U$1") (pin "6") (pinfunction "GND_6") (pintype "bidirectional"))
      (node (ref "U$10") (pin "6") (pinfunction "GND_6") (pintype "bidirectional"))
      (node (ref "U$11") (pin "6") (pinfunction "GND_6") (pintype "bidirectional"))
      (node (ref "U$12") (pin "6") (pinfunction "GND_6") (pintype "bidirectional"))
      (node (ref "U$13") (pin "6") (pinfunction "GND_6") (pintype "bidirectional"))
      (node (ref "U$14") (pin "6") (pinfunction "GND_6") (pintype "bidirectional"))
      (node (ref "U$15") (pin "6") (pinfunction "GND_6") (pintype "bidirectional"))
      (node (ref "U$16") (pin "6") (pinfunction "GND_6") (pintype "bidirectional"))
      (node (ref "U$17") (pin "6") (pinfunction "GND_6") (pintype "bidirectional"))
      (node (ref "U$18") (pin "6") (pinfunction "GND_6") (pintype "bidirectional"))
      (node (ref "U$19") (pin "6") (pinfunction "GND_6") (pintype "bidirectional"))
      (node (ref "U$2") (pin "6") (pinfunction "GND_6") (pintype "bidirectional"))
      (node (ref "U$20") (pin "6") (pinfunction "GND_6") (pintype "bidirectional"))
      (node (ref "U$21") (pin "6") (pinfunction "GND_6") (pintype "bidirectional"))
      (node (ref "U$22") (pin "6") (pinfunction "GND_6") (pintype "bidirectional"))
      (node (ref "U$23") (pin "6") (pinfunction "GND_6") (pintype "bidirectional"))
      (node (ref "U$24") (pin "6") (pinfunction "GND_6") (pintype "bidirectional"))
      (node (ref "U$25") (pin "6") (pinfunction "GND_6") (pintype "bidirectional"))
      (node (ref "U$26") (pin "6") (pinfunction "GND_6") (pintype "bidirectional"))
      (node (ref "U$27") (pin "6") (pinfunction "GND_6") (pintype "bidirectional"))
      (node (ref "U$28") (pin "6") (pinfunction "GND_6") (pintype "bidirectional"))
      (node (ref "U$29") (pin "6") (pinfunction "GND_6") (pintype "bidirectional"))
      (node (ref "U$3") (pin "6") (pinfunction "GND_6") (pintype "bidirectional"))
      (node (ref "U$30") (pin "6") (pinfunction "GND_6") (pintype "bidirectional"))
      (node (ref "U$31") (pin "6") (pinfunction "GND_6") (pintype "bidirectional"))
      (node (ref "U$32") (pin "6") (pinfunction "GND_6") (pintype "bidirectional"))
      (node (ref "U$33") (pin "6") (pinfunction "GND_6") (pintype "bidirectional"))
      (node (ref "U$34") (pin "6") (pinfunction "GND_6") (pintype "bidirectional"))
      (node (ref "U$35") (pin "6") (pinfunction "GND_6") (pintype "bidirectional"))
      (node (ref "U$36") (pin "6") (pinfunction "GND_6") (pintype "bidirectional"))
      (node (ref "U$37") (pin "6") (pinfunction "GND_6") (pintype "bidirectional"))
      (node (ref "U$38") (pin "6") (pinfunction "GND_6") (pintype "bidirectional"))
      (node (ref "U$39") (pin "6") (pinfunction "GND_6") (pintype "bidirectional"))
      (node (ref "U$4") (pin "6") (pinfunction "GND_6") (pintype "bidirectional"))
      (node (ref "U$40") (pin "6") (pinfunction "GND_6") (pintype "bidirectional"))
      (node (ref "U$41") (pin "6") (pinfunction "GND_6") (pintype "bidirectional"))
      (node (ref "U$42") (pin "6") (pinfunction "GND_6") (pintype "bidirectional"))
      (node (ref "U$43") (pin "6") (pinfunction "GND_6") (pintype "bidirectional"))
      (node (ref "U$44") (pin "6") (pinfunction "GND_6") (pintype "bidirectional"))
      (node (ref "U$45") (pin "6") (pinfunction "GND_6") (pintype "bidirectional"))
      (node (ref "U$46") (pin "6") (pinfunction "GND_6") (pintype "bidirectional"))
      (node (ref "U$47") (pin "6") (pinfunction "GND_6") (pintype "bidirectional"))
      (node (ref "U$5") (pin "6") (pinfunction "GND_6") (pintype "bidirectional"))
      (node (ref "U$6") (pin "6") (pinfunction "GND_6") (pintype "bidirectional"))
      (node (ref "U$7") (pin "6") (pinfunction "GND_6") (pintype "bidirectional"))
      (node (ref "U$8") (pin "6") (pinfunction "GND_6") (pintype "bidirectional"))
      (node (ref "U$9") (pin "6") (pinfunction "GND_6") (pintype "bidirectional"))
    )
    (net (code "4") (name "Net-(CI-P)") (class "Default")
      (node (ref "CI") (pin "1") (pinfunction "P_1") (pintype "passive"))
      (node (ref "U$40") (pin "5") (pinfunction "CI_5") (pintype "bidirectional"))
    )
    (net (code "5") (name "Net-(CO-P)") (class "Default")
      (node (ref "CO") (pin "1") (pinfunction "P_1") (pintype "passive"))
      (node (ref "U$39") (pin "2") (pinfunction "CO_2") (pintype "bidirectional"))
    )
    (net (code "6") (name "Net-(DI-P)") (class "Default")
      (node (ref "DI") (pin "1") (pinfunction "P_1") (pintype "passive"))
      (node (ref "U$40") (pin "4") (pinfunction "DI_4") (pintype "bidirectional"))
    )
    (net (code "7") (name "Net-(DO-P)") (class "Default")
      (node (ref "DO") (pin "1") (pinfunction "P_1") (pintype "passive"))
      (node (ref "U$39") (pin "3") (pinfunction "DO_3") (pintype "bidirectional"))
    )
    (net (code "8") (name "Net-(U$1-CI)") (class "Default")
      (node (ref "U$1") (pin "5") (pinfunction "CI_5") (pintype "bidirectional"))
      (node (ref "U$47") (pin "2") (pinfunction "CO_2") (pintype "bidirectional"))
    )
    (net (code "9") (name "Net-(U$1-CO)") (class "Default")
      (node (ref "U$1") (pin "2") (pinfunction "CO_2") (pintype "bidirectional"))
      (node (ref "U$2") (pin "5") (pinfunction "CI_5") (pintype "bidirectional"))
    )
    (net (code "10") (name "Net-(U$1-DI)") (class "Default")
      (node (ref "U$1") (pin "4") (pinfunction "DI_4") (pintype "bidirectional"))
      (node (ref "U$47") (pin "3") (pinfunction "DO_3") (pintype "bidirectional"))
    )
    (net (code "11") (name "Net-(U$1-DO)") (class "Default")
      (node (ref "U$1") (pin "3") (pinfunction "DO_3") (pintype "bidirectional"))
      (node (ref "U$2") (pin "4") (pinfunction "DI_4") (pintype "bidirectional"))
    )
    (net (code "12") (name "Net-(U$2-CO)") (class "Default")
      (node (ref "U$2") (pin "2") (pinfunction "CO_2") (pintype "bidirectional"))
      (node (ref "U$3") (pin "5") (pinfunction "CI_5") (pintype "bidirectional"))
    )
    (net (code "13") (name "Net-(U$2-DO)") (class "Default")
      (node (ref "U$2") (pin "3") (pinfunction "DO_3") (pintype "bidirectional"))
      (node (ref "U$3") (pin "4") (pinfunction "DI_4") (pintype "bidirectional"))
    )
    (net (code "14") (name "Net-(U$3-CO)") (class "Default")
      (node (ref "U$3") (pin "2") (pinfunction "CO_2") (pintype "bidirectional"))
      (node (ref "U$4") (pin "5") (pinfunction "CI_5") (pintype "bidirectional"))
    )
    (net (code "15") (name "Net-(U$3-DO)") (class "Default")
      (node (ref "U$3") (pin "3") (pinfunction "DO_3") (pintype "bidirectional"))
      (node (ref "U$4") (pin "4") (pinfunction "DI_4") (pintype "bidirectional"))
    )
    (net (code "16") (name "Net-(U$4-CO)") (class "Default")
      (node (ref "U$4") (pin "2") (pinfunction "CO_2") (pintype "bidirectional"))
      (node (ref "U$5") (pin "5") (pinfunction "CI_5") (pintype "bidirectional"))
    )
    (net (code "17") (name "Net-(U$4-DO)") (class "Default")
      (node (ref "U$4") (pin "3") (pinfunction "DO_3") (pintype "bidirectional"))
      (node (ref "U$5") (pin "4") (pinfunction "DI_4") (pintype "bidirectional"))
    )
    (net (code "18") (name "Net-(U$5-CO)") (class "Default")
      (node (ref "U$5") (pin "2") (pinfunction "CO_2") (pintype "bidirectional"))
      (node (ref "U$6") (pin "5") (pinfunction "CI_5") (pintype "bidirectional"))
    )
    (net (code "19") (name "Net-(U$5-DO)") (class "Default")
      (node (ref "U$5") (pin "3") (pinfunction "DO_3") (pintype "bidirectional"))
      (node (ref "U$6") (pin "4") (pinfunction "DI_4") (pintype "bidirectional"))
    )
    (net (code "20") (name "Net-(U$6-CO)") (class "Default")
      (node (ref "U$6") (pin "2") (pinfunction "CO_2") (pintype "bidirectional"))
      (node (ref "U$7") (pin "5") (pinfunction "CI_5") (pintype "bidirectional"))
    )
    (net (code "21") (name "Net-(U$6-DO)") (class "Default")
      (node (ref "U$6") (pin "3") (pinfunction "DO_3") (pintype "bidirectional"))
      (node (ref "U$7") (pin "4") (pinfunction "DI_4") (pintype "bidirectional"))
    )
    (net (code "22") (name "Net-(U$7-CO)") (class "Default")
      (node (ref "U$7") (pin "2") (pinfunction "CO_2") (pintype "bidirectional"))
      (node (ref "U$8") (pin "5") (pinfunction "CI_5") (pintype "bidirectional"))
    )
    (net (code "23") (name "Net-(U$7-DO)") (class "Default")
      (node (ref "U$7") (pin "3") (pinfunction "DO_3") (pintype "bidirectional"))
      (node (ref "U$8") (pin "4") (pinfunction "DI_4") (pintype "bidirectional"))
    )
    (net (code "24") (name "Net-(U$8-CO)") (class "Default")
      (node (ref "U$8") (pin "2") (pinfunction "CO_2") (pintype "bidirectional"))
      (node (ref "U$9") (pin "5") (pinfunction "CI_5") (pintype "bidirectional"))
    )
    (net (code "25") (name "Net-(U$8-DO)") (class "Default")
      (node (ref "U$8") (pin "3") (pinfunction "DO_3") (pintype "bidirectional"))
      (node (ref "U$9") (pin "4") (pinfunction "DI_4") (pintype "bidirectional"))
    )
    (net (code "26") (name "Net-(U$10-CI)") (class "Default")
      (node (ref "U$10") (pin "5") (pinfunction "CI_5") (pintype "bidirectional"))
      (node (ref "U$9") (pin "2") (pinfunction "CO_2") (pintype "bidirectional"))
    )
    (net (code "27") (name "Net-(U$10-CO)") (class "Default")
      (node (ref "U$10") (pin "2") (pinfunction "CO_2") (pintype "bidirectional"))
      (node (ref "U$11") (pin "5") (pinfunction "CI_5") (pintype "bidirectional"))
    )
    (net (code "28") (name "Net-(U$10-DI)") (class "Default")
      (node (ref "U$10") (pin "4") (pinfunction "DI_4") (pintype "bidirectional"))
      (node (ref "U$9") (pin "3") (pinfunction "DO_3") (pintype "bidirectional"))
    )
    (net (code "29") (name "Net-(U$10-DO)") (class "Default")
      (node (ref "U$10") (pin "3") (pinfunction "DO_3") (pintype "bidirectional"))
      (node (ref "U$11") (pin "4") (pinfunction "DI_4") (pintype "bidirectional"))
    )
    (net (code "30") (name "Net-(U$11-CO)") (class "Default")
      (node (ref "U$11") (pin "2") (pinfunction "CO_2") (pintype "bidirectional"))
      (node (ref "U$12") (pin "5") (pinfunction "CI_5") (pintype "bidirectional"))
    )
    (net (code "31") (name "Net-(U$11-DO)") (class "Default")
      (node (ref "U$11") (pin "3") (pinfunction "DO_3") (pintype "bidirectional"))
      (node (ref "U$12") (pin "4") (pinfunction "DI_4") (pintype "bidirectional"))
    )
    (net (code "32") (name "Net-(U$12-CO)") (class "Default")
      (node (ref "U$12") (pin "2") (pinfunction "CO_2") (pintype "bidirectional"))
      (node (ref "U$13") (pin "5") (pinfunction "CI_5") (pintype "bidirectional"))
    )
    (net (code "33") (name "Net-(U$12-DO)") (class "Default")
      (node (ref "U$12") (pin "3") (pinfunction "DO_3") (pintype "bidirectional"))
      (node (ref "U$13") (pin "4") (pinfunction "DI_4") (pintype "bidirectional"))
    )
    (net (code "34") (name "Net-(U$13-CO)") (class "Default")
      (node (ref "U$13") (pin "2") (pinfunction "CO_2") (pintype "bidirectional"))
      (node (ref "U$14") (pin "5") (pinfunction "CI_5") (pintype "bidirectional"))
    )
    (net (code "35") (name "Net-(U$13-DO)") (class "Default")
      (node (ref "U$13") (pin "3") (pinfunction "DO_3") (pintype "bidirectional"))
      (node (ref "U$14") (pin "4") (pinfunction "DI_4") (pintype "bidirectional"))
    )
    (net (code "36") (name "Net-(U$14-CO)") (class "Default")
      (node (ref "U$14") (pin "2") (pinfunction "CO_2") (pintype "bidirectional"))
      (node (ref "U$15") (pin "5") (pinfunction "CI_5") (pintype "bidirectional"))
    )
    (net (code "37") (name "Net-(U$14-DO)") (class "Default")
      (node (ref "U$14") (pin "3") (pinfunction "DO_3") (pintype "bidirectional"))
      (node (ref "U$15") (pin "4") (pinfunction "DI_4") (pintype "bidirectional"))
    )
    (net (code "38") (name "Net-(U$15-CO)") (class "Default")
      (node (ref "U$15") (pin "2") (pinfunction "CO_2") (pintype "bidirectional"))
      (node (ref "U$16") (pin "5") (pinfunction "CI_5") (pintype "bidirectional"))
    )
    (net (code "39") (name "Net-(U$15-DO)") (class "Default")
      (node (ref "U$15") (pin "3") (pinfunction "DO_3") (pintype "bidirectional"))
      (node (ref "U$16") (pin "4") (pinfunction "DI_4") (pintype "bidirectional"))
    )
    (net (code "40") (name "Net-(U$16-CO)") (class "Default")
      (node (ref "U$16") (pin "2") (pinfunction "CO_2") (pintype "bidirectional"))
      (node (ref "U$17") (pin "5") (pinfunction "CI_5") (pintype "bidirectional"))
    )
    (net (code "41") (name "Net-(U$16-DO)") (class "Default")
      (node (ref "U$16") (pin "3") (pinfunction "DO_3") (pintype "bidirectional"))
      (node (ref "U$17") (pin "4") (pinfunction "DI_4") (pintype "bidirectional"))
    )
    (net (code "42") (name "Net-(U$17-CO)") (class "Default")
      (node (ref "U$17") (pin "2") (pinfunction "CO_2") (pintype "bidirectional"))
      (node (ref "U$18") (pin "5") (pinfunction "CI_5") (pintype "bidirectional"))
    )
    (net (code "43") (name "Net-(U$17-DO)") (class "Default")
      (node (ref "U$17") (pin "3") (pinfunction "DO_3") (pintype "bidirectional"))
      (node (ref "U$18") (pin "4") (pinfunction "DI_4") (pintype "bidirectional"))
    )
    (net (code "44") (name "Net-(U$18-CO)") (class "Default")
      (node (ref "U$18") (pin "2") (pinfunction "CO_2") (pintype "bidirectional"))
      (node (ref "U$19") (pin "5") (pinfunction "CI_5") (pintype "bidirectional"))
    )
    (net (code "45") (name "Net-(U$18-DO)") (class "Default")
      (node (ref "U$18") (pin "3") (pinfunction "DO_3") (pintype "bidirectional"))
      (node (ref "U$19") (pin "4") (pinfunction "DI_4") (pintype "bidirectional"))
    )
    (net (code "46") (name "Net-(U$19-CO)") (class "Default")
      (node (ref "U$19") (pin "2") (pinfunction "CO_2") (pintype "bidirectional"))
      (node (ref "U$20") (pin "5") (pinfunction "CI_5") (pintype "bidirectional"))
    )
    (net (code "47") (name "Net-(U$19-DO)") (class "Default")
      (node (ref "U$19") (pin "3") (pinfunction "DO_3") (pintype "bidirectional"))
      (node (ref "U$20") (pin "4") (pinfunction "DI_4") (pintype "bidirectional"))
    )
    (net (code "48") (name "Net-(U$20-CO)") (class "Default")
      (node (ref "U$20") (pin "2") (pinfunction "CO_2") (pintype "bidirectional"))
      (node (ref "U$21") (pin "5") (pinfunction "CI_5") (pintype "bidirectional"))
    )
    (net (code "49") (name "Net-(U$20-DO)") (class "Default")
      (node (ref "U$20") (pin "3") (pinfunction "DO_3") (pintype "bidirectional"))
      (node (ref "U$21") (pin "4") (pinfunction "DI_4") (pintype "bidirectional"))
    )
    (net (code "50") (name "Net-(U$21-CO)") (class "Default")
      (node (ref "U$21") (pin "2") (pinfunction "CO_2") (pintype "bidirectional"))
      (node (ref "U$22") (pin "5") (pinfunction "CI_5") (pintype "bidirectional"))
    )
    (net (code "51") (name "Net-(U$21-DO)") (class "Default")
      (node (ref "U$21") (pin "3") (pinfunction "DO_3") (pintype "bidirectional"))
      (node (ref "U$22") (pin "4") (pinfunction "DI_4") (pintype "bidirectional"))
    )
    (net (code "52") (name "Net-(U$22-CO)") (class "Default")
      (node (ref "U$22") (pin "2") (pinfunction "CO_2") (pintype "bidirectional"))
      (node (ref "U$23") (pin "5") (pinfunction "CI_5") (pintype "bidirectional"))
    )
    (net (code "53") (name "Net-(U$22-DO)") (class "Default")
      (node (ref "U$22") (pin "3") (pinfunction "DO_3") (pintype "bidirectional"))
      (node (ref "U$23") (pin "4") (pinfunction "DI_4") (pintype "bidirectional"))
    )
    (net (code "54") (name "Net-(U$23-CO)") (class "Default")
      (node (ref "U$23") (pin "2") (pinfunction "CO_2") (pintype "bidirectional"))
      (node (ref "U$24") (pin "5") (pinfunction "CI_5") (pintype "bidirectional"))
    )
    (net (code "55") (name "Net-(U$23-DO)") (class "Default")
      (node (ref "U$23") (pin "3") (pinfunction "DO_3") (pintype "bidirectional"))
      (node (ref "U$24") (pin "4") (pinfunction "DI_4") (pintype "bidirectional"))
    )
    (net (code "56") (name "Net-(U$24-CO)") (class "Default")
      (node (ref "U$24") (pin "2") (pinfunction "CO_2") (pintype "bidirectional"))
      (node (ref "U$25") (pin "5") (pinfunction "CI_5") (pintype "bidirectional"))
    )
    (net (code "57") (name "Net-(U$24-DO)") (class "Default")
      (node (ref "U$24") (pin "3") (pinfunction "DO_3") (pintype "bidirectional"))
      (node (ref "U$25") (pin "4") (pinfunction "DI_4") (pintype "bidirectional"))
    )
    (net (code "58") (name "Net-(U$25-CO)") (class "Default")
      (node (ref "U$25") (pin "2") (pinfunction "CO_2") (pintype "bidirectional"))
      (node (ref "U$26") (pin "5") (pinfunction "CI_5") (pintype "bidirectional"))
    )
    (net (code "59") (name "Net-(U$25-DO)") (class "Default")
      (node (ref "U$25") (pin "3") (pinfunction "DO_3") (pintype "bidirectional"))
      (node (ref "U$26") (pin "4") (pinfunction "DI_4") (pintype "bidirectional"))
    )
    (net (code "60") (name "Net-(U$26-CO)") (class "Default")
      (node (ref "U$26") (pin "2") (pinfunction "CO_2") (pintype "bidirectional"))
      (node (ref "U$27") (pin "5") (pinfunction "CI_5") (pintype "bidirectional"))
    )
    (net (code "61") (name "Net-(U$26-DO)") (class "Default")
      (node (ref "U$26") (pin "3") (pinfunction "DO_3") (pintype "bidirectional"))
      (node (ref "U$27") (pin "4") (pinfunction "DI_4") (pintype "bidirectional"))
    )
    (net (code "62") (name "Net-(U$27-CO)") (class "Default")
      (node (ref "U$27") (pin "2") (pinfunction "CO_2") (pintype "bidirectional"))
      (node (ref "U$28") (pin "5") (pinfunction "CI_5") (pintype "bidirectional"))
    )
    (net (code "63") (name "Net-(U$27-DO)") (class "Default")
      (node (ref "U$27") (pin "3") (pinfunction "DO_3") (pintype "bidirectional"))
      (node (ref "U$28") (pin "4") (pinfunction "DI_4") (pintype "bidirectional"))
    )
    (net (code "64") (name "Net-(U$28-CO)") (class "Default")
      (node (ref "U$28") (pin "2") (pinfunction "CO_2") (pintype "bidirectional"))
      (node (ref "U$29") (pin "5") (pinfunction "CI_5") (pintype "bidirectional"))
    )
    (net (code "65") (name "Net-(U$28-DO)") (class "Default")
      (node (ref "U$28") (pin "3") (pinfunction "DO_3") (pintype "bidirectional"))
      (node (ref "U$29") (pin "4") (pinfunction "DI_4") (pintype "bidirectional"))
    )
    (net (code "66") (name "Net-(U$29-CO)") (class "Default")
      (node (ref "U$29") (pin "2") (pinfunction "CO_2") (pintype "bidirectional"))
      (node (ref "U$30") (pin "5") (pinfunction "CI_5") (pintype "bidirectional"))
    )
    (net (code "67") (name "Net-(U$29-DO)") (class "Default")
      (node (ref "U$29") (pin "3") (pinfunction "DO_3") (pintype "bidirectional"))
      (node (ref "U$30") (pin "4") (pinfunction "DI_4") (pintype "bidirectional"))
    )
    (net (code "68") (name "Net-(U$30-CO)") (class "Default")
      (node (ref "U$30") (pin "2") (pinfunction "CO_2") (pintype "bidirectional"))
      (node (ref "U$31") (pin "5") (pinfunction "CI_5") (pintype "bidirectional"))
    )
    (net (code "69") (name "Net-(U$30-DO)") (class "Default")
      (node (ref "U$30") (pin "3") (pinfunction "DO_3") (pintype "bidirectional"))
      (node (ref "U$31") (pin "4") (pinfunction "DI_4") (pintype "bidirectional"))
    )
    (net (code "70") (name "Net-(U$31-CO)") (class "Default")
      (node (ref "U$31") (pin "2") (pinfunction "CO_2") (pintype "bidirectional"))
      (node (ref "U$32") (pin "5") (pinfunction "CI_5") (pintype "bidirectional"))
    )
    (net (code "71") (name "Net-(U$31-DO)") (class "Default")
      (node (ref "U$31") (pin "3") (pinfunction "DO_3") (pintype "bidirectional"))
      (node (ref "U$32") (pin "4") (pinfunction "DI_4") (pintype "bidirectional"))
    )
    (net (code "72") (name "Net-(U$32-CO)") (class "Default")
      (node (ref "U$32") (pin "2") (pinfunction "CO_2") (pintype "bidirectional"))
      (node (ref "U$33") (pin "5") (pinfunction "CI_5") (pintype "bidirectional"))
    )
    (net (code "73") (name "Net-(U$32-DO)") (class "Default")
      (node (ref "U$32") (pin "3") (pinfunction "DO_3") (pintype "bidirectional"))
      (node (ref "U$33") (pin "4") (pinfunction "DI_4") (pintype "bidirectional"))
    )
    (net (code "74") (name "Net-(U$33-CO)") (class "Default")
      (node (ref "U$33") (pin "2") (pinfunction "CO_2") (pintype "bidirectional"))
      (node (ref "U$34") (pin "5") (pinfunction "CI_5") (pintype "bidirectional"))
    )
    (net (code "75") (name "Net-(U$33-DO)") (class "Default")
      (node (ref "U$33") (pin "3") (pinfunction "DO_3") (pintype "bidirectional"))
      (node (ref "U$34") (pin "4") (pinfunction "DI_4") (pintype "bidirectional"))
    )
    (net (code "76") (name "Net-(U$34-CO)") (class "Default")
      (node (ref "U$34") (pin "2") (pinfunction "CO_2") (pintype "bidirectional"))
      (node (ref "U$35") (pin "5") (pinfunction "CI_5") (pintype "bidirectional"))
    )
    (net (code "77") (name "Net-(U$34-DO)") (class "Default")
      (node (ref "U$34") (pin "3") (pinfunction "DO_3") (pintype "bidirectional"))
      (node (ref "U$35") (pin "4") (pinfunction "DI_4") (pintype "bidirectional"))
    )
    (net (code "78") (name "Net-(U$35-CO)") (class "Default")
      (node (ref "U$35") (pin "2") (pinfunction "CO_2") (pintype "bidirectional"))
      (node (ref "U$36") (pin "5") (pinfunction "CI_5") (pintype "bidirectional"))
    )
    (net (code "79") (name "Net-(U$35-DO)") (class "Default")
      (node (ref "U$35") (pin "3") (pinfunction "DO_3") (pintype "bidirectional"))
      (node (ref "U$36") (pin "4") (pinfunction "DI_4") (pintype "bidirectional"))
    )
    (net (code "80") (name "Net-(U$36-CO)") (class "Default")
      (node (ref "U$36") (pin "2") (pinfunction "CO_2") (pintype "bidirectional"))
      (node (ref "U$37") (pin "5") (pinfunction "CI_5") (pintype "bidirectional"))
    )
    (net (code "81") (name "Net-(U$36-DO)") (class "Default")
      (node (ref "U$36") (pin "3") (pinfunction "DO_3") (pintype "bidirectional"))
      (node (ref "U$37") (pin "4") (pinfunction "DI_4") (pintype "bidirectional"))
    )
    (net (code "82") (name "Net-(U$37-CO)") (class "Default")
      (node (ref "U$37") (pin "2") (pinfunction "CO_2") (pintype "bidirectional"))
      (node (ref "U$38") (pin "5") (pinfunction "CI_5") (pintype "bidirectional"))
    )
    (net (code "83") (name "Net-(U$37-DO)") (class "Default")
      (node (ref "U$37") (pin "3") (pinfunction "DO_3") (pintype "bidirectional"))
      (node (ref "U$38") (pin "4") (pinfunction "DI_4") (pintype "bidirectional"))
    )
    (net (code "84") (name "Net-(U$38-CO)") (class "Default")
      (node (ref "U$38") (pin "2") (pinfunction "CO_2") (pintype "bidirectional"))
      (node (ref "U$39") (pin "5") (pinfunction "CI_5") (pintype "bidirectional"))
    )
    (net (code "85") (name "Net-(U$38-DO)") (class "Default")
      (node (ref "U$38") (pin "3") (pinfunction "DO_3") (pintype "bidirectional"))
      (node (ref "U$39") (pin "4") (pinfunction "DI_4") (pintype "bidirectional"))
    )
    (net (code "86") (name "Net-(U$40-CO)") (class "Default")
      (node (ref "U$40") (pin "2") (pinfunction "CO_2") (pintype "bidirectional"))
      (node (ref "U$41") (pin "5") (pinfunction "CI_5") (pintype "bidirectional"))
    )
    (net (code "87") (name "Net-(U$40-DO)") (class "Default")
      (node (ref "U$40") (pin "3") (pinfunction "DO_3") (pintype "bidirectional"))
      (node (ref "U$41") (pin "4") (pinfunction "DI_4") (pintype "bidirectional"))
    )
    (net (code "88") (name "Net-(U$41-CO)") (class "Default")
      (node (ref "U$41") (pin "2") (pinfunction "CO_2") (pintype "bidirectional"))
      (node (ref "U$42") (pin "5") (pinfunction "CI_5") (pintype "bidirectional"))
    )
    (net (code "89") (name "Net-(U$41-DO)") (class "Default")
      (node (ref "U$41") (pin "3") (pinfunction "DO_3") (pintype "bidirectional"))
      (node (ref "U$42") (pin "4") (pinfunction "DI_4") (pintype "bidirectional"))
    )
    (net (code "90") (name "Net-(U$42-CO)") (class "Default")
      (node (ref "U$42") (pin "2") (pinfunction "CO_2") (pintype "bidirectional"))
      (node (ref "U$43") (pin "5") (pinfunction "CI_5") (pintype "bidirectional"))
    )
    (net (code "91") (name "Net-(U$42-DO)") (class "Default")
      (node (ref "U$42") (pin "3") (pinfunction "DO_3") (pintype "bidirectional"))
      (node (ref "U$43") (pin "4") (pinfunction "DI_4") (pintype "bidirectional"))
    )
    (net (code "92") (name "Net-(U$43-CO)") (class "Default")
      (node (ref "U$43") (pin "2") (pinfunction "CO_2") (pintype "bidirectional"))
      (node (ref "U$44") (pin "5") (pinfunction "CI_5") (pintype "bidirectional"))
    )
    (net (code "93") (name "Net-(U$43-DO)") (class "Default")
      (node (ref "U$43") (pin "3") (pinfunction "DO_3") (pintype "bidirectional"))
      (node (ref "U$44") (pin "4") (pinfunction "DI_4") (pintype "bidirectional"))
    )
    (net (code "94") (name "Net-(U$44-CO)") (class "Default")
      (node (ref "U$44") (pin "2") (pinfunction "CO_2") (pintype "bidirectional"))
      (node (ref "U$45") (pin "5") (pinfunction "CI_5") (pintype "bidirectional"))
    )
    (net (code "95") (name "Net-(U$44-DO)") (class "Default")
      (node (ref "U$44") (pin "3") (pinfunction "DO_3") (pintype "bidirectional"))
      (node (ref "U$45") (pin "4") (pinfunction "DI_4") (pintype "bidirectional"))
    )
    (net (code "96") (name "Net-(U$45-CO)") (class "Default")
      (node (ref "U$45") (pin "2") (pinfunction "CO_2") (pintype "bidirectional"))
      (node (ref "U$46") (pin "5") (pinfunction "CI_5") (pintype "bidirectional"))
    )
    (net (code "97") (name "Net-(U$45-DO)") (class "Default")
      (node (ref "U$45") (pin "3") (pinfunction "DO_3") (pintype "bidirectional"))
      (node (ref "U$46") (pin "4") (pinfunction "DI_4") (pintype "bidirectional"))
    )
    (net (code "98") (name "Net-(U$46-CO)") (class "Default")
      (node (ref "U$46") (pin "2") (pinfunction "CO_2") (pintype "bidirectional"))
      (node (ref "U$47") (pin "5") (pinfunction "CI_5") (pintype "bidirectional"))
    )
    (net (code "99") (name "Net-(U$46-DO)") (class "Default")
      (node (ref "U$46") (pin "3") (pinfunction "DO_3") (pintype "bidirectional"))
      (node (ref "U$47") (pin "4") (pinfunction "DI_4") (pintype "bidirectional"))
    )
    (net (code "100") (name "unconnected-(IC1-ADJ-Pad1)") (class "Default")
      (node (ref "IC1") (pin "1") (pinfunction "ADJ_1") (pintype "passive"))
    )
  )
)
